# sheet.net
KiCad netlist of a schematic drawn in Altium Designer
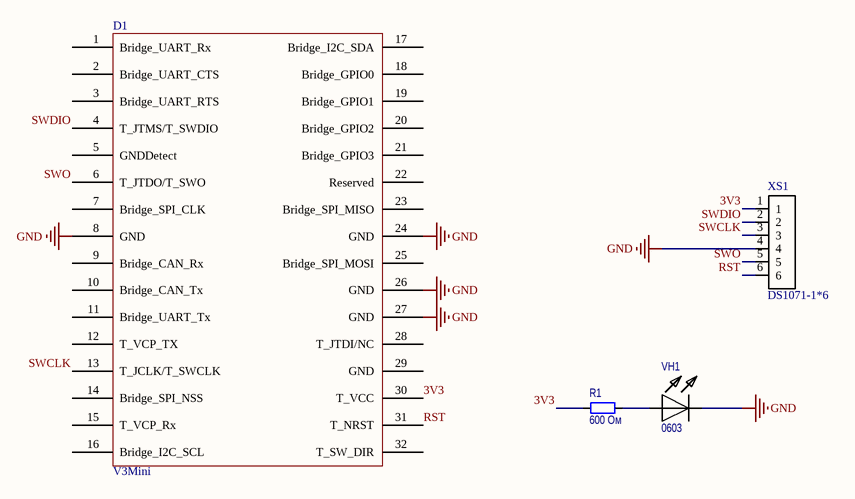
[diagram p0: sheet.SchDoc]

(export (version "E")
  (design (tool "Eeschema 10.0.6"))
  (components
    (comp (ref "D1") (value "V3Mini") (footprint "STV3Mini") (libsource (lib "MyLib") (part "V3Mini")))
    (comp (ref "R1")
      (value "600 Ом")
      (footprint "Passive components:0805")
      (description "Resistor")
      (libsource (lib "AleksandrVasinLib") (part "RESISTOR"))
    )
    (comp (ref "VH1")
      (value "0603")
      (footprint "led_0603")
      (fields (field (name "PART NUMBER") "TO-1608BC-MRE"))
      (libsource (lib "AleksandrVasinLib") (part "led"))
    )
    (comp (ref "XS1")
      (value "DS1071-1*6")
      (footprint "PBS-6R")
      (description "6 pin 1 row socket")
      (libsource (lib "MyLib") (part "PBS-6(DS1023-1*6)"))
    )
  )
  (nets
    (net (code "1") (name "/3V3") (class "Default")
      (node (ref "D1") (pin "30") (pinfunction "T_VCC_30") (pintype "passive"))
      (node (ref "R1") (pin "1") (pinfunction "1_1") (pintype "passive"))
      (node (ref "XS1") (pin "1") (pinfunction "1_1") (pintype "passive"))
    )
    (net (code "2") (name "/RST") (class "Default")
      (node (ref "D1") (pin "31") (pinfunction "T_NRST_31") (pintype "passive"))
      (node (ref "XS1") (pin "6") (pinfunction "6_6") (pintype "passive"))
    )
    (net (code "3") (name "/SWCLK") (class "Default")
      (node (ref "D1") (pin "13") (pinfunction "T_JCLK/T_SWCLK_13") (pintype "passive"))
      (node (ref "XS1") (pin "3") (pinfunction "3_3") (pintype "passive"))
    )
    (net (code "4") (name "/SWDIO") (class "Default")
      (node (ref "D1") (pin "4") (pinfunction "T_JTMS/T_SWDIO_4") (pintype "passive"))
      (node (ref "XS1") (pin "2") (pinfunction "2_2") (pintype "passive"))
    )
    (net (code "5") (name "/SWO") (class "Default")
      (node (ref "D1") (pin "6") (pinfunction "T_JTDO/T_SWO_6") (pintype "passive"))
      (node (ref "XS1") (pin "5") (pinfunction "5_5") (pintype "passive"))
    )
    (net (code "6") (name "GND") (class "Default")
      (node (ref "D1") (pin "24") (pinfunction "GND_24") (pintype "passive"))
      (node (ref "D1") (pin "26") (pinfunction "GND_26") (pintype "passive"))
      (node (ref "D1") (pin "27") (pinfunction "GND_27") (pintype "passive"))
      (node (ref "D1") (pin "8") (pinfunction "GND_8") (pintype "passive"))
      (node (ref "VH1") (pin "1") (pinfunction "Cathode_1") (pintype "passive"))
      (node (ref "XS1") (pin "4") (pinfunction "4_4") (pintype "passive"))
    )
    (net (code "7") (name "Net-(VH1-Anode)") (class "Default")
      (node (ref "R1") (pin "2") (pinfunction "2_2") (pintype "passive"))
      (node (ref "VH1") (pin "2") (pinfunction "Anode_2") (pintype "passive"))
    )
    (net (code "8") (name "unconnected-(D1-Bridge_CAN_Rx-Pad9)") (class "Default")
      (node (ref "D1") (pin "9") (pinfunction "Bridge_CAN_Rx_9") (pintype "passive"))
    )
    (net (code "9") (name "unconnected-(D1-Bridge_CAN_Tx-Pad10)") (class "Default")
      (node (ref "D1") (pin "10") (pinfunction "Bridge_CAN_Tx_10") (pintype "passive"))
    )
    (net (code "10") (name "unconnected-(D1-Bridge_GPIO0-Pad18)") (class "Default")
      (node (ref "D1") (pin "18") (pinfunction "Bridge_GPIO0_18") (pintype "passive"))
    )
    (net (code "11") (name "unconnected-(D1-Bridge_GPIO1-Pad19)") (class "Default")
      (node (ref "D1") (pin "19") (pinfunction "Bridge_GPIO1_19") (pintype "passive"))
    )
    (net (code "12") (name "unconnected-(D1-Bridge_GPIO2-Pad20)") (class "Default")
      (node (ref "D1") (pin "20") (pinfunction "Bridge_GPIO2_20") (pintype "passive"))
    )
    (net (code "13") (name "unconnected-(D1-Bridge_GPIO3-Pad21)") (class "Default")
      (node (ref "D1") (pin "21") (pinfunction "Bridge_GPIO3_21") (pintype "passive"))
    )
    (net (code "14") (name "unconnected-(D1-Bridge_I2C_SCL-Pad16)") (class "Default")
      (node (ref "D1") (pin "16") (pinfunction "Bridge_I2C_SCL_16") (pintype "passive"))
    )
    (net (code "15") (name "unconnected-(D1-Bridge_I2C_SDA-Pad17)") (class "Default")
      (node (ref "D1") (pin "17") (pinfunction "Bridge_I2C_SDA_17") (pintype "passive"))
    )
    (net (code "16") (name "unconnected-(D1-Bridge_SPI_CLK-Pad7)") (class "Default")
      (node (ref "D1") (pin "7") (pinfunction "Bridge_SPI_CLK_7") (pintype "passive"))
    )
    (net (code "17") (name "unconnected-(D1-Bridge_SPI_MISO-Pad23)") (class "Default")
      (node (ref "D1") (pin "23") (pinfunction "Bridge_SPI_MISO_23") (pintype "passive"))
    )
    (net (code "18") (name "unconnected-(D1-Bridge_SPI_MOSI-Pad25)") (class "Default")
      (node (ref "D1") (pin "25") (pinfunction "Bridge_SPI_MOSI_25") (pintype "passive"))
    )
    (net (code "19") (name "unconnected-(D1-Bridge_SPI_NSS-Pad14)") (class "Default")
      (node (ref "D1") (pin "14") (pinfunction "Bridge_SPI_NSS_14") (pintype "passive"))
    )
    (net (code "20") (name "unconnected-(D1-Bridge_UART_CTS-Pad2)") (class "Default")
      (node (ref "D1") (pin "2") (pinfunction "Bridge_UART_CTS_2") (pintype "passive"))
    )
    (net (code "21") (name "unconnected-(D1-Bridge_UART_RTS-Pad3)") (class "Default")
      (node (ref "D1") (pin "3") (pinfunction "Bridge_UART_RTS_3") (pintype "passive"))
    )
    (net (code "22") (name "unconnected-(D1-Bridge_UART_Rx-Pad1)") (class "Default")
      (node (ref "D1") (pin "1") (pinfunction "Bridge_UART_Rx_1") (pintype "passive"))
    )
    (net (code "23") (name "unconnected-(D1-Bridge_UART_Tx-Pad11)") (class "Default")
      (node (ref "D1") (pin "11") (pinfunction "Bridge_UART_Tx_11") (pintype "passive"))
    )
    (net (code "24") (name "unconnected-(D1-GND-Pad29)") (class "Default")
      (node (ref "D1") (pin "29") (pinfunction "GND_29") (pintype "passive"))
    )
    (net (code "25") (name "unconnected-(D1-GNDDetect-Pad5)") (class "Default")
      (node (ref "D1") (pin "5") (pinfunction "GNDDetect_5") (pintype "passive"))
    )
    (net (code "26") (name "unconnected-(D1-Reserved-Pad22)") (class "Default")
      (node (ref "D1") (pin "22") (pinfunction "Reserved_22") (pintype "passive"))
    )
    (net (code "27") (name "unconnected-(D1-T_JTDI{slash}NC-Pad28)") (class "Default")
      (node (ref "D1") (pin "28") (pinfunction "T_JTDI/NC_28") (pintype "passive"))
    )
    (net (code "28") (name "unconnected-(D1-T_SW_DIR-Pad32)") (class "Default")
      (node (ref "D1") (pin "32") (pinfunction "T_SW_DIR_32") (pintype "passive"))
    )
    (net (code "29") (name "unconnected-(D1-T_VCP_Rx-Pad15)") (class "Default")
      (node (ref "D1") (pin "15") (pinfunction "T_VCP_Rx_15") (pintype "passive"))
    )
    (net (code "30") (name "unconnected-(D1-T_VCP_TX-Pad12)") (class "Default")
      (node (ref "D1") (pin "12") (pinfunction "T_VCP_TX_12") (pintype "passive"))
    )
  )
)
